# AD9363_OSCILLATORS.net
KiCad netlist of a schematic drawn in Altium Designer
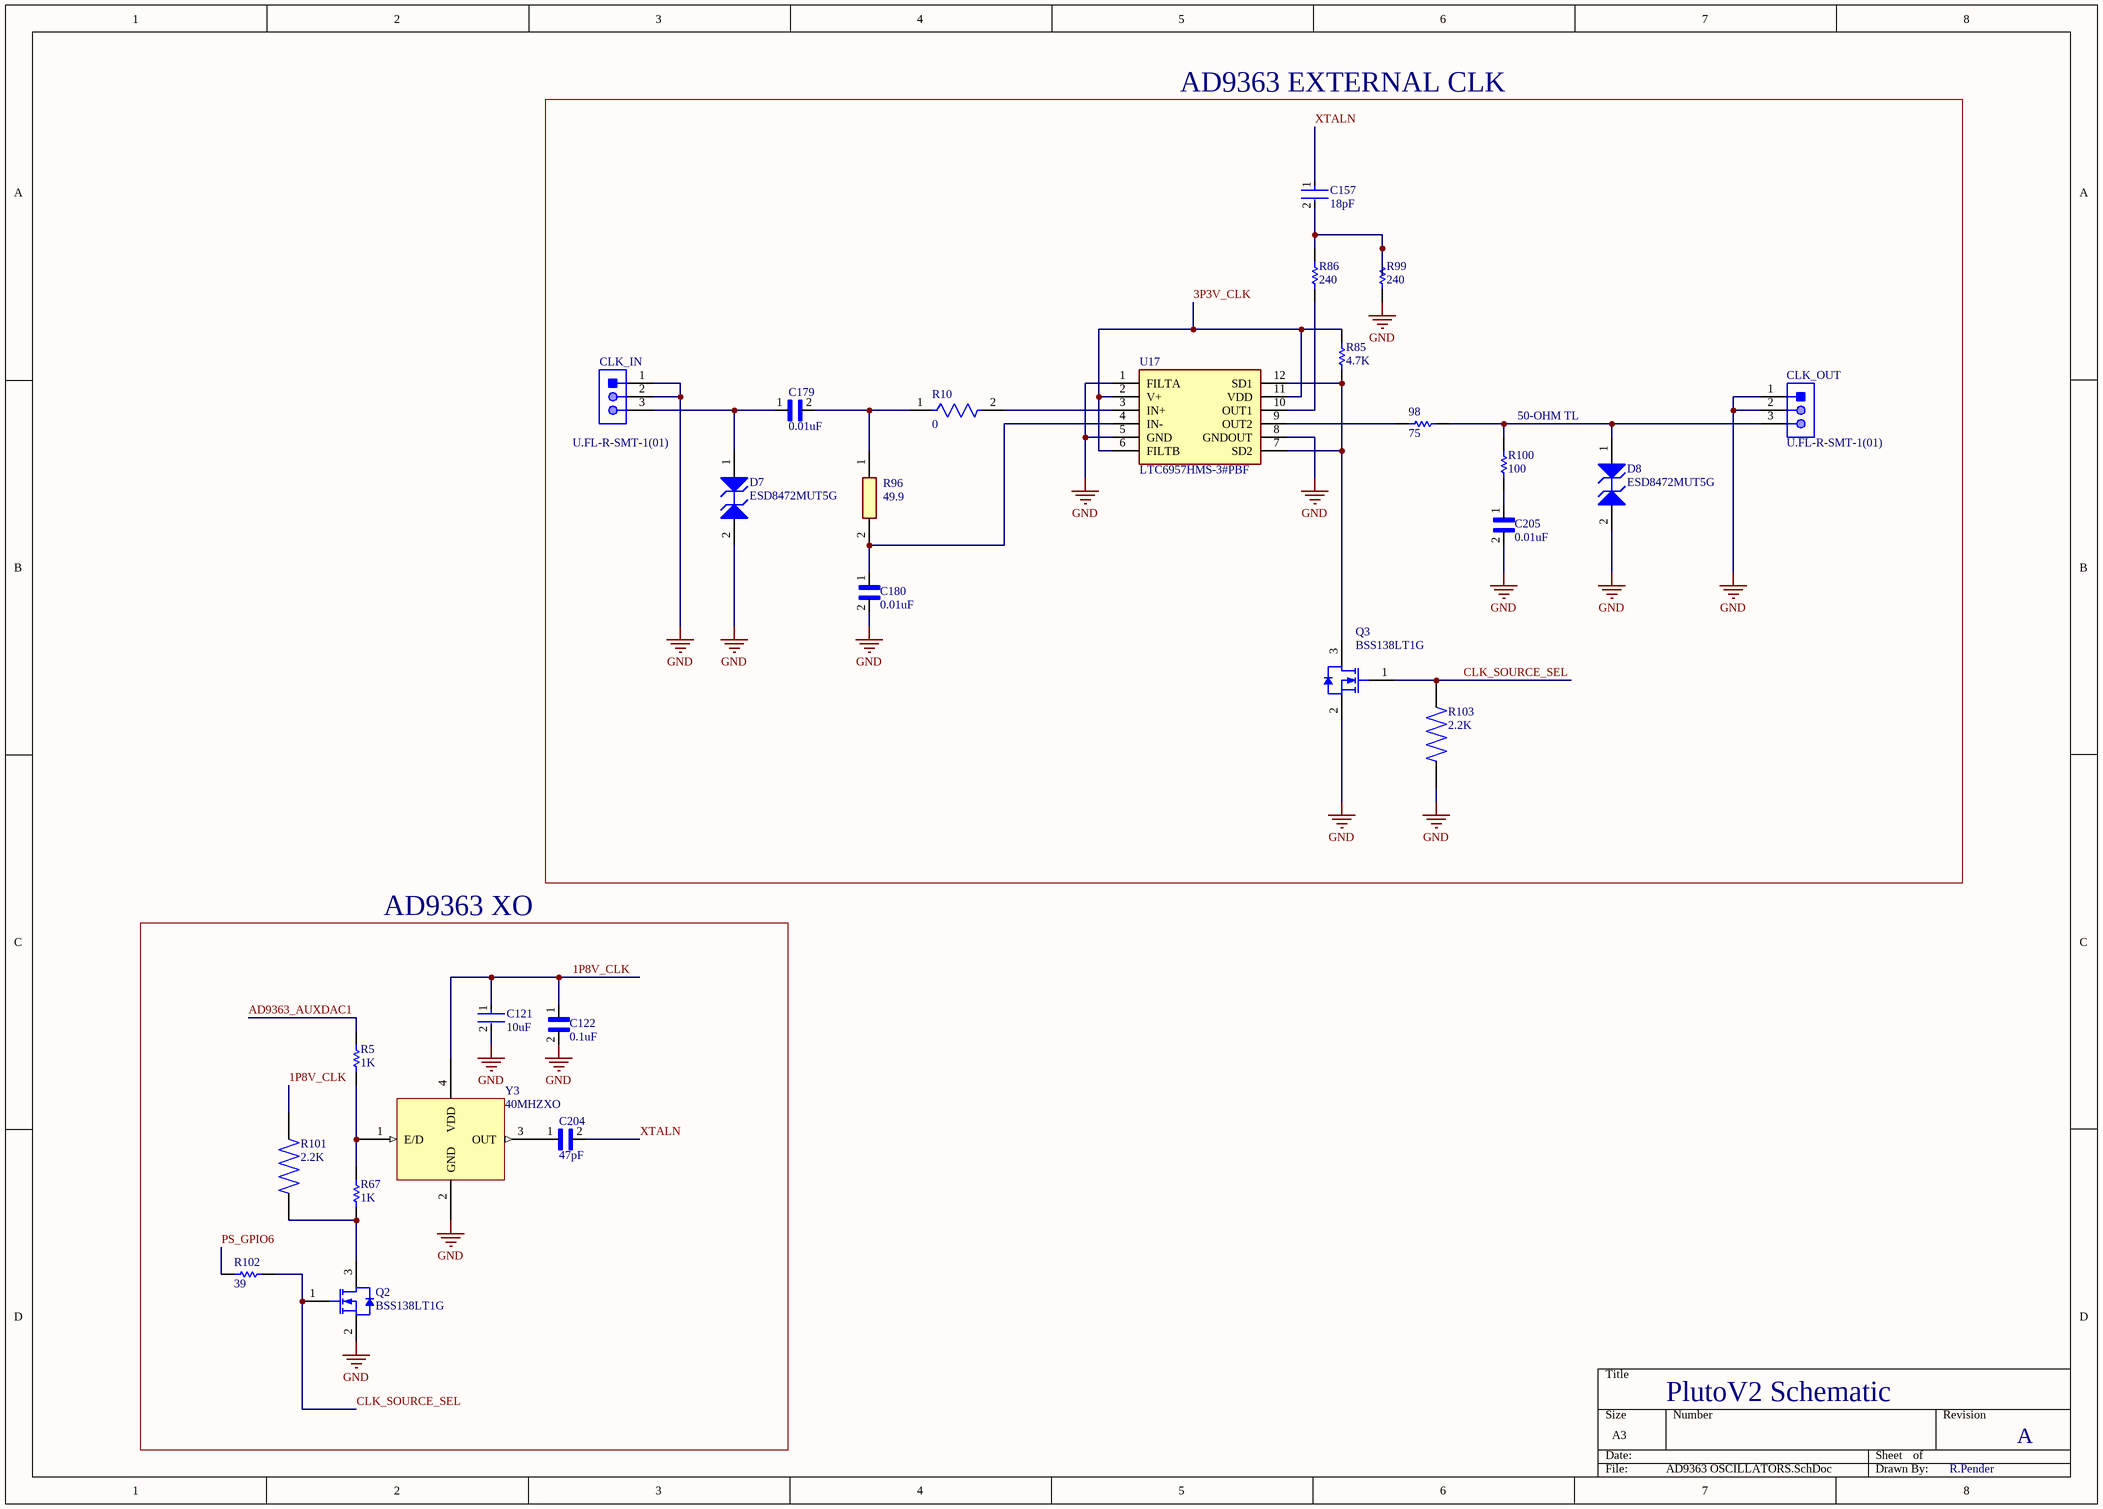
[diagram p0: AD9363 OSCILLATORS.SchDoc]

(export (version "E")
  (design (tool "Eeschema 10.0.6"))
  (components
    (comp (ref "98")
      (value "75")
      (footprint "2-0402")
      (fields (field (name "PUBLISHER") "Altium Limited"))
      (libsource (lib "Panasonic Resistor") (part "ERJ2RK"))
    )
    (comp (ref "C121")
      (value "10uF")
      (footprint "FP-GRM188-0_1-e0_2_0_55-IPC_C")
      (description "Chip Multilayer Ceramic Capacitors for General Purpose, 0603, 10uF, X5R, 15%, 20%, 6.3V")
      (fields (field (name "VOLTAGE") "6.3V") (field (name "TOLERANCE") "20%"))
      (libsource (lib "Altium Content Vault") (part "02cd4be3c70576c341d710602a673aa"))
    )
    (comp (ref "C122")
      (value "0.1uF")
      (footprint "CAPC0603X33N")
      (description "CAP 0.1UF 16VDC X5R 20% SMD 0201 PAPER TAPE")
      (fields (field (name "MP") "GRM033R61C104ME84D"))
      (libsource (lib "GRM033R61C104ME84D") (part "GRM033R61C104ME84D"))
    )
    (comp (ref "C157")
      (value "18pF")
      (footprint "FP-GRM033-0_03-IPC_A")
      (description "Chip Multilayer Ceramic Capacitors for General Purpose, 0201, 18pF, C0G, 30ppm/°C, 5%, 50V")
      (fields (field (name "TOLERANCE") "5%") (field (name "VOLTAGE") "50V"))
      (libsource (lib "Altium Content Vault") (part "b4654b650e69147ec39a6b967a45e02"))
    )
    (comp (ref "C179")
      (value "0.01uF")
      (footprint "CAPC0603X33N")
      (description "SMD Capacitor X7R(EIA) with Capacitance: 10000pF Tol. 10%. Rated Voltage: 10Vdc")
      (fields (field (name "MP") "GRM033R71A103KA01D") (field (name "MF") "Murata"))
      (libsource (lib "") (part "GRM033R71A103KA01D_1"))
    )
    (comp (ref "C180")
      (value "0.01uF")
      (footprint "CAPC0603X33N")
      (description "SMD Capacitor X7R(EIA) with Capacitance: 10000pF Tol. 10%. Rated Voltage: 10Vdc")
      (fields (field (name "MP") "GRM033R71A103KA01D") (field (name "MF") "Murata"))
      (libsource (lib "GRM033R71A103KA01D") (part "GRM033R71A103KA01D"))
    )
    (comp (ref "C204")
      (value "47pF")
      (footprint "CAPC1005X55N")
      (description "47pF Â±5% 50V Ceramic Capacitor C0G, NP0 0402 (1005 Metric)")
      (fields (field (name "MP") "GCM1555C1H470JA16D") (field (name "MF") "Murata"))
      (libsource (lib "GCM1555C1H470JA16D") (part "GCM1555C1H470JA16D"))
    )
    (comp (ref "C205")
      (value "0.01uF")
      (footprint "CAPC0603X33N")
      (description "SMD Capacitor X7R(EIA) with Capacitance: 10000pF Tol. 10%. Rated Voltage: 10Vdc")
      (fields (field (name "MP") "GRM033R71A103KA01D") (field (name "MF") "Murata"))
      (libsource (lib "GRM033R71A103KA01D") (part "GRM033R71A103KA01D"))
    )
    (comp (ref "CLK_IN")
      (value "U.FL-R-SMT-1(01)")
      (footprint "HRS-U.FL-R-SMT-3_V")
      (description "Ultra Small Coaxial Connector, 6 GHz, -40 to 90 degC, 3-Pin SMD, RoHS, Bulk")
      (fields (field (name "MANUFACTURER") "Hirose Electric"))
      (libsource (lib "") (part "CN-1P-M-R3_1"))
    )
    (comp (ref "CLK_OUT")
      (value "U.FL-R-SMT-1(01)")
      (footprint "HRS-U.FL-R-SMT-3_V")
      (description "Ultra Small Coaxial Connector, 6 GHz, -40 to 90 degC, 3-Pin SMD, RoHS, Bulk")
      (fields (field (name "MANUFACTURER") "Hirose Electric"))
      (libsource (lib "Altium Content Vault") (part "CN-1P-M-R3"))
    )
    (comp (ref "D7")
      (value "ESD8472MUT5G")
      (footprint "ONSC-X3DFN-2-152AF-01_V")
      (fields (field (name "MANUFACTURER") "On Semiconductor"))
      (libsource (lib "Altium Content Vault") (part "ONSC-A1A2-2"))
    )
    (comp (ref "D8")
      (value "ESD8472MUT5G")
      (footprint "ONSC-X3DFN-2-152AF-01_V")
      (fields (field (name "MANUFACTURER") "On Semiconductor"))
      (libsource (lib "Altium Content Vault") (part "ONSC-A1A2-2"))
    )
    (comp (ref "Q2")
      (value "BSS138LT1G")
      (footprint "ONSC-SOT-23-3-318-08_V")
      (description "Power MOSFET, 200 mA, 50 V, N-Channel, 3-Pin SOT-23, Pb-Free, Tape and Reel")
      (fields (field (name "MANUFACTURER") "On Semiconductor"))
      (libsource (lib "Altium Content Vault") (part "ONSC-NMOS-G1S2D3-3"))
    )
    (comp (ref "Q3")
      (value "BSS138LT1G")
      (footprint "ONSC-SOT-23-3-318-08_V")
      (description "Power MOSFET, 200 mA, 50 V, N-Channel, 3-Pin SOT-23, Pb-Free, Tape and Reel")
      (fields (field (name "MANUFACTURER") "On Semiconductor"))
      (libsource (lib "Altium Content Vault") (part "ONSC-NMOS-G1S2D3-3"))
    )
    (comp (ref "R5")
      (value "1K")
      (footprint "RESC0603X26X15NL03T05")
      (fields (field (name "MANUFACTURER") "Panasonic") (field (name "PART NUMBER") "ERJ1GNF10R0C"))
      (libsource (lib "Altium Content Vault") (part "RES"))
    )
    (comp (ref "R10")
      (value "0")
      (footprint "FP-ERJ1GN-IPC_A")
      (description "RES SMD 0 OHM JUMPER 1/20W 0201")
      (fields (field (name "TOLERANCE") "1%"))
      (libsource (lib "Altium Content Vault") (part "1029c3af85768c4190bb7ad29bc67b5"))
    )
    (comp (ref "R67")
      (value "1K")
      (footprint "2-0402")
      (fields (field (name "PUBLISHER") "Altium Limited"))
      (libsource (lib "Panasonic Resistor") (part "ERJ2RK"))
    )
    (comp (ref "R85")
      (value "4.7K")
      (footprint "2-0402")
      (fields (field (name "PUBLISHER") "Altium Limited"))
      (libsource (lib "Panasonic Resistor") (part "ERJ2RK"))
    )
    (comp (ref "R86")
      (value "240")
      (footprint "2-0402")
      (fields (field (name "PUBLISHER") "Altium Limited"))
      (libsource (lib "Panasonic Resistor") (part "ERJ2RK"))
    )
    (comp (ref "R96")
      (value "49.9")
      (footprint "SamacSys:RESC1608X46N")
      (description "Resistor")
      (fields (field (name "MANUFACTURER_PART_NUMBER") "PCAN0603E49R9BST5"))
      (libsource (lib "*") (part "PCAN0603E49R9BST5"))
    )
    (comp (ref "R99")
      (value "240")
      (footprint "2-0402")
      (fields (field (name "PUBLISHER") "Altium Limited"))
      (libsource (lib "Panasonic Resistor") (part "ERJ2RK"))
    )
    (comp (ref "R100")
      (value "100")
      (footprint "2-0402")
      (fields (field (name "PUBLISHER") "Altium Limited"))
      (libsource (lib "Panasonic Resistor") (part "ERJ2RK"))
    )
    (comp (ref "R101")
      (value "2.2K")
      (footprint "RESC1005X35N")
      (description "2.2 kOhms Â±1% 0.063W, 1/16W Chip Resistor 0402 _1005 Metric_ Thick Film")
      (fields (field (name "MF") "Vishay") (field (name "MP") "CRCW04022K20FKEDC"))
      (libsource (lib "CRCW04022K20FKEDC") (part "CRCW04022K20FKEDC"))
    )
    (comp (ref "R102")
      (value "39")
      (footprint "2-0402")
      (description "Thick Film Chip Resistor, 1 Ohm to 2.2M Ohm Range, 5% Tolerance, 0402 Size, 0.063 W")
      (fields (field (name "PUBLISHER") "Altium Limited"))
      (libsource (lib "Panasonic Resistor") (part "ERJ2GE"))
    )
    (comp (ref "R103")
      (value "2.2K")
      (footprint "RESC1005X35N")
      (description "2.2 kOhms Â±1% 0.063W, 1/16W Chip Resistor 0402 _1005 Metric_ Thick Film")
      (fields (field (name "MF") "Vishay") (field (name "MP") "CRCW04022K20FKEDC"))
      (libsource (lib "CRCW04022K20FKEDC") (part "CRCW04022K20FKEDC"))
    )
    (comp (ref "U17")
      (value "LTC6957HMS-3#PBF")
      (footprint "SamacSys:SOP65P490X110-12N")
      (description "Integrated Circuit")
      (fields (field (name "MOUSER2 PART NUMBER") "584-LTC6957HMS-3#PBF"))
      (libsource (lib "*") (part "LTC6957HMS-3#PBF"))
    )
    (comp (ref "Y3")
      (value "40MHZXO")
      (footprint "XO40MHz")
      (libsource (lib "RINALDOSCHEMS") (part "40MHZXO"))
    )
  )
  (nets
    (net (code "1") (name "/1P8V_CLK") (class "Default")
      (node (ref "C121") (pin "1") (pinfunction "1_1") (pintype "passive"))
      (node (ref "C122") (pin "1") (pinfunction "1_1") (pintype "passive"))
      (node (ref "R101") (pin "2") (pinfunction "2_2") (pintype "passive"))
      (node (ref "Y3") (pin "4") (pinfunction "VDD_4") (pintype "passive"))
    )
    (net (code "2") (name "/3P3V_CLK") (class "Default")
      (node (ref "R85") (pin "2") (pinfunction "2_2") (pintype "passive"))
      (node (ref "U17") (pin "11") (pinfunction "VDD_11") (pintype "passive"))
      (node (ref "U17") (pin "2") (pinfunction "V+_2") (pintype "passive"))
      (node (ref "U17") (pin "6") (pinfunction "FILTB_6") (pintype "passive"))
    )
    (net (code "3") (name "/AD9363_AUXDAC1") (class "Default")
      (node (ref "R5") (pin "1") (pinfunction "1_1") (pintype "passive"))
    )
    (net (code "4") (name "/CLK_SOURCE_SEL") (class "Default")
      (node (ref "Q2") (pin "1") (pinfunction "G_1") (pintype "passive"))
      (node (ref "Q3") (pin "1") (pinfunction "G_1") (pintype "passive"))
      (node (ref "R102") (pin "2") (pinfunction "2_2") (pintype "passive"))
      (node (ref "R103") (pin "1") (pinfunction "1_1") (pintype "passive"))
    )
    (net (code "5") (name "/PS_GPIO6") (class "Default")
      (node (ref "R102") (pin "1") (pinfunction "1_1") (pintype "passive"))
    )
    (net (code "6") (name "/XTALN") (class "Default")
      (node (ref "C157") (pin "1") (pinfunction "1_1") (pintype "passive"))
      (node (ref "C204") (pin "2") (pinfunction "2_2") (pintype "passive"))
    )
    (net (code "7") (name "GND") (class "Default")
      (node (ref "C121") (pin "2") (pinfunction "2_2") (pintype "passive"))
      (node (ref "C122") (pin "2") (pinfunction "2_2") (pintype "passive"))
      (node (ref "C180") (pin "2") (pinfunction "2_2") (pintype "passive"))
      (node (ref "C205") (pin "2") (pinfunction "2_2") (pintype "passive"))
      (node (ref "CLK_IN") (pin "1") (pinfunction "1_1") (pintype "passive"))
      (node (ref "CLK_IN") (pin "2") (pinfunction "2_2") (pintype "passive"))
      (node (ref "CLK_OUT") (pin "1") (pinfunction "1_1") (pintype "passive"))
      (node (ref "CLK_OUT") (pin "2") (pinfunction "2_2") (pintype "passive"))
      (node (ref "D7") (pin "2") (pinfunction "A2_2") (pintype "passive"))
      (node (ref "D8") (pin "2") (pinfunction "A2_2") (pintype "passive"))
      (node (ref "Q2") (pin "2") (pinfunction "S_2") (pintype "passive"))
      (node (ref "Q3") (pin "2") (pinfunction "S_2") (pintype "passive"))
      (node (ref "R103") (pin "2") (pinfunction "2_2") (pintype "passive"))
      (node (ref "R99") (pin "1") (pinfunction "1_1") (pintype "passive"))
      (node (ref "U17") (pin "1") (pinfunction "FILTA_1") (pintype "passive"))
      (node (ref "U17") (pin "5") (pinfunction "GND_5") (pintype "passive"))
      (node (ref "U17") (pin "8") (pinfunction "GNDOUT_8") (pintype "passive"))
      (node (ref "Y3") (pin "2") (pinfunction "GND_2") (pintype "power_in"))
    )
    (net (code "8") (name "Net-(C157-Pad2)") (class "Default")
      (node (ref "C157") (pin "2") (pinfunction "2_2") (pintype "passive"))
      (node (ref "R86") (pin "2") (pinfunction "2_2") (pintype "passive"))
      (node (ref "R99") (pin "2") (pinfunction "2_2") (pintype "passive"))
    )
    (net (code "9") (name "Net-(C179-Pad2)") (class "Default")
      (node (ref "C179") (pin "2") (pinfunction "2_2") (pintype "passive"))
      (node (ref "R10") (pin "1") (pinfunction "1_1") (pintype "passive"))
      (node (ref "R96") (pin "1") (pinfunction "1_1") (pintype "passive"))
    )
    (net (code "10") (name "Net-(C205-Pad1)") (class "Default")
      (node (ref "C205") (pin "1") (pinfunction "1_1") (pintype "passive"))
      (node (ref "R100") (pin "2") (pinfunction "2_2") (pintype "passive"))
    )
    (net (code "11") (name "Net-(D7-A1)") (class "Default")
      (node (ref "C179") (pin "1") (pinfunction "1_1") (pintype "passive"))
      (node (ref "CLK_IN") (pin "3") (pinfunction "3_3") (pintype "passive"))
      (node (ref "D7") (pin "1") (pinfunction "A1_1") (pintype "passive"))
    )
    (net (code "12") (name "Net-(D8-A1)") (class "Default")
      (node (ref "98") (pin "2") (pinfunction "2_2") (pintype "passive"))
      (node (ref "CLK_OUT") (pin "3") (pinfunction "3_3") (pintype "passive"))
      (node (ref "D8") (pin "1") (pinfunction "A1_1") (pintype "passive"))
      (node (ref "R100") (pin "1") (pinfunction "1_1") (pintype "passive"))
    )
    (net (code "13") (name "Net-(Q2-D)") (class "Default")
      (node (ref "Q2") (pin "3") (pinfunction "D_3") (pintype "passive"))
      (node (ref "R101") (pin "1") (pinfunction "1_1") (pintype "passive"))
      (node (ref "R67") (pin "2") (pinfunction "2_2") (pintype "passive"))
    )
    (net (code "14") (name "Net-(Q3-D)") (class "Default")
      (node (ref "Q3") (pin "3") (pinfunction "D_3") (pintype "passive"))
      (node (ref "R85") (pin "1") (pinfunction "1_1") (pintype "passive"))
      (node (ref "U17") (pin "12") (pinfunction "SD1_12") (pintype "passive"))
      (node (ref "U17") (pin "7") (pinfunction "SD2_7") (pintype "passive"))
    )
    (net (code "15") (name "Net-(U17-IN+)") (class "Default")
      (node (ref "R10") (pin "2") (pinfunction "2_2") (pintype "passive"))
      (node (ref "U17") (pin "3") (pinfunction "IN+_3") (pintype "passive"))
    )
    (net (code "16") (name "Net-(U17-IN-)") (class "Default")
      (node (ref "C180") (pin "1") (pinfunction "1_1") (pintype "passive"))
      (node (ref "R96") (pin "2") (pinfunction "2_2") (pintype "passive"))
      (node (ref "U17") (pin "4") (pinfunction "IN-_4") (pintype "passive"))
    )
    (net (code "17") (name "Net-(U17-OUT1)") (class "Default")
      (node (ref "R86") (pin "1") (pinfunction "1_1") (pintype "passive"))
      (node (ref "U17") (pin "10") (pinfunction "OUT1_10") (pintype "passive"))
    )
    (net (code "18") (name "Net-(U17-OUT2)") (class "Default")
      (node (ref "98") (pin "1") (pinfunction "1_1") (pintype "passive"))
      (node (ref "U17") (pin "9") (pinfunction "OUT2_9") (pintype "passive"))
    )
    (net (code "19") (name "Net-(Y3-E{slash}D)") (class "Default")
      (node (ref "R5") (pin "2") (pinfunction "2_2") (pintype "passive"))
      (node (ref "R67") (pin "1") (pinfunction "1_1") (pintype "passive"))
      (node (ref "Y3") (pin "1") (pinfunction "E/D_1") (pintype "input"))
    )
    (net (code "20") (name "Net-(Y3-OUT)") (class "Default")
      (node (ref "C204") (pin "1") (pinfunction "1_1") (pintype "passive"))
      (node (ref "Y3") (pin "3") (pinfunction "OUT_3") (pintype "output"))
    )
  )
)
